# SWD.net
KiCad netlist of a schematic drawn in Altium Designer
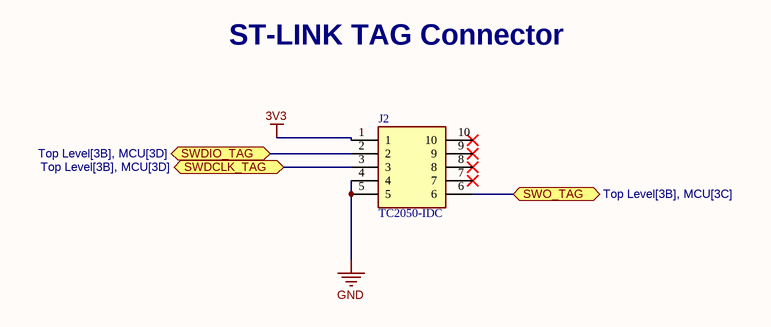
[diagram p0: SWD.SchDoc]

(export (version "E")
  (design (tool "Eeschema 10.0.6"))
  (components
    (comp (ref "J2")
      (value "TC2050-IDC")
      (footprint "TC2050-IDC")
      (description "Connector")
      (libsource (lib "C2S") (part "TC2050-IDC"))
    )
  )
  (nets
    (net (code "1") (name "/SWDCLK_TAG") (class "Default")
      (node (ref "J2") (pin "3") (pinfunction "3_3") (pintype "passive"))
    )
    (net (code "2") (name "/SWDIO_TAG") (class "Default")
      (node (ref "J2") (pin "2") (pinfunction "2_2") (pintype "passive"))
    )
    (net (code "3") (name "/SWO_TAG") (class "Default")
      (node (ref "J2") (pin "6") (pinfunction "6_6") (pintype "passive"))
    )
    (net (code "4") (name "3V3") (class "Default")
      (node (ref "J2") (pin "1") (pinfunction "1_1") (pintype "passive"))
    )
    (net (code "5") (name "GND") (class "Default")
      (node (ref "J2") (pin "4") (pinfunction "4_4") (pintype "passive"))
      (node (ref "J2") (pin "5") (pinfunction "5_5") (pintype "passive"))
    )
    (net (code "6") (name "unconnected-(J2-Pad7)") (class "Default")
      (node (ref "J2") (pin "7") (pinfunction "7_7") (pintype "passive+no_connect"))
    )
    (net (code "7") (name "unconnected-(J2-Pad8)") (class "Default")
      (node (ref "J2") (pin "8") (pinfunction "8_8") (pintype "passive+no_connect"))
    )
    (net (code "8") (name "unconnected-(J2-Pad9)") (class "Default")
      (node (ref "J2") (pin "9") (pinfunction "9_9") (pintype "passive+no_connect"))
    )
    (net (code "9") (name "unconnected-(J2-Pad10)") (class "Default")
      (node (ref "J2") (pin "10") (pinfunction "10_10") (pintype "passive+no_connect"))
    )
  )
)
